# RCJ_com_v2.net
KiCad netlist of a schematic drawn in EAGLE
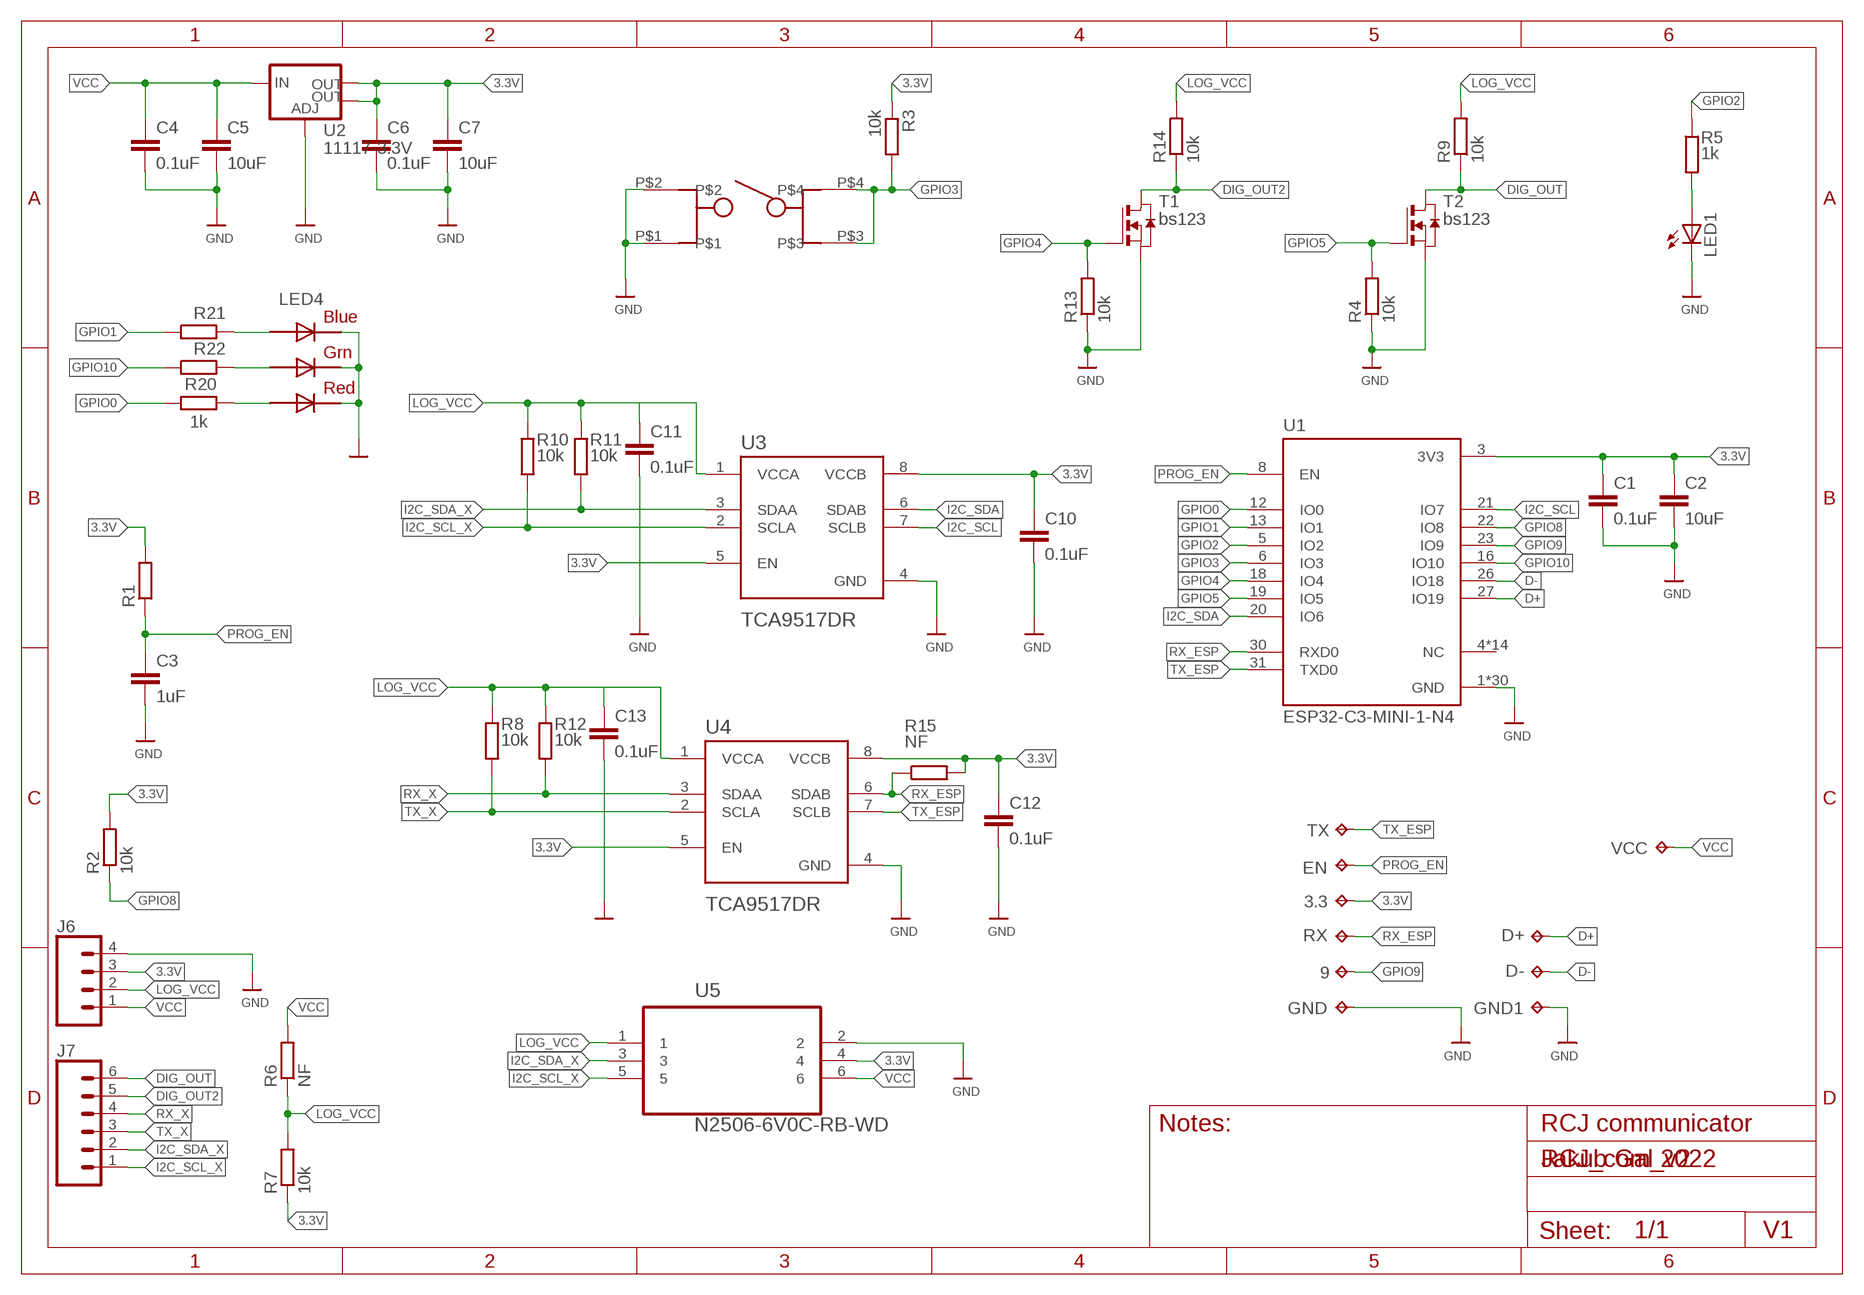
[diagram p0: schematic, sheet 1]

(export (version "E")
  (design (tool "Eeschema 10.0.6"))
  (components
    (comp (ref "3.3")
      (value "TPTP08R")
      (footprint "eagle-import:TP08R")
      (libsource (lib "eagle-import") (part "TPTP08R"))
    )
    (comp (ref "9")
      (value "TPTP08R")
      (footprint "eagle-import:TP08R")
      (libsource (lib "eagle-import") (part "TPTP08R"))
    )
    (comp (ref "C1")
      (value "0.1uF")
      (footprint "eagle-import:C0402K")
      (libsource (lib "eagle-import") (part "C-EUC0402K"))
    )
    (comp (ref "C2")
      (value "10uF")
      (footprint "eagle-import:C0402K")
      (libsource (lib "eagle-import") (part "C-EUC0402K"))
    )
    (comp (ref "C3")
      (value "1uF")
      (footprint "eagle-import:C0402K")
      (libsource (lib "eagle-import") (part "C-EUC0402K"))
    )
    (comp (ref "C4")
      (value "0.1uF")
      (footprint "eagle-import:C0402K")
      (libsource (lib "eagle-import") (part "C-EUC0402K"))
    )
    (comp (ref "C5")
      (value "10uF")
      (footprint "eagle-import:C0402K")
      (libsource (lib "eagle-import") (part "C-EUC0402K"))
    )
    (comp (ref "C6")
      (value "0.1uF")
      (footprint "eagle-import:C0402K")
      (libsource (lib "eagle-import") (part "C-EUC0402K"))
    )
    (comp (ref "C7")
      (value "10uF")
      (footprint "eagle-import:C0402K")
      (libsource (lib "eagle-import") (part "C-EUC0402K"))
    )
    (comp (ref "C10")
      (value "0.1uF")
      (footprint "eagle-import:C0402K")
      (libsource (lib "eagle-import") (part "C-EUC0402K"))
    )
    (comp (ref "C11")
      (value "0.1uF")
      (footprint "eagle-import:C0402K")
      (libsource (lib "eagle-import") (part "C-EUC0402K"))
    )
    (comp (ref "C12")
      (value "0.1uF")
      (footprint "eagle-import:C0402K")
      (libsource (lib "eagle-import") (part "C-EUC0402K"))
    )
    (comp (ref "C13")
      (value "0.1uF")
      (footprint "eagle-import:C0402K")
      (libsource (lib "eagle-import") (part "C-EUC0402K"))
    )
    (comp (ref "D+")
      (value "TPTP08R")
      (footprint "eagle-import:TP08R")
      (libsource (lib "eagle-import") (part "TPTP08R"))
    )
    (comp (ref "D-")
      (value "TPTP08R")
      (footprint "eagle-import:TP08R")
      (libsource (lib "eagle-import") (part "TPTP08R"))
    )
    (comp (ref "EN")
      (value "TPTP08R")
      (footprint "eagle-import:TP08R")
      (libsource (lib "eagle-import") (part "TPTP08R"))
    )
    (comp (ref "GND")
      (value "TPTP08R")
      (footprint "eagle-import:TP08R")
      (libsource (lib "eagle-import") (part "TPTP08R"))
    )
    (comp (ref "GND1")
      (value "TPTP08R")
      (footprint "eagle-import:TP08R")
      (libsource (lib "eagle-import") (part "TPTP08R"))
    )
    (comp (ref "J6")
      (value "CONN_04")
      (footprint "eagle-import:1X04")
      (libsource (lib "eagle-import") (part "CONN_04"))
    )
    (comp (ref "J7")
      (value "CONN_06SILK_FEMALE_PTH")
      (footprint "eagle-import:1X06")
      (libsource (lib "eagle-import") (part "CONN_06SILK_FEMALE_PTH"))
    )
    (comp (ref "LED1")
      (value "0603_Led")
      (footprint "eagle-import:CHIPLED_0603")
      (libsource (lib "eagle-import") (part "LEDCHIPLED_0603"))
    )
    (comp (ref "LED4")
      (value "RGBLED5050")
      (footprint "eagle-import:RGBLED5050")
      (libsource (lib "eagle-import") (part "RGBLED5050"))
    )
    (comp (ref "R1")
      (value "10k")
      (footprint "eagle-import:R0402")
      (libsource (lib "eagle-import") (part "R-EU_R0402"))
    )
    (comp (ref "R2")
      (value "10k")
      (footprint "eagle-import:R0402")
      (libsource (lib "eagle-import") (part "R-EU_R0402"))
    )
    (comp (ref "R3")
      (value "10k")
      (footprint "eagle-import:R0402")
      (libsource (lib "eagle-import") (part "R-EU_R0402"))
    )
    (comp (ref "R4")
      (value "10k")
      (footprint "eagle-import:R0402")
      (libsource (lib "eagle-import") (part "R-EU_R0402"))
    )
    (comp (ref "R5")
      (value "1k")
      (footprint "eagle-import:R0402")
      (libsource (lib "eagle-import") (part "R-EU_R0402"))
    )
    (comp (ref "R6")
      (value "NF")
      (footprint "eagle-import:R0402")
      (libsource (lib "eagle-import") (part "R-EU_R0402"))
    )
    (comp (ref "R7")
      (value "10k")
      (footprint "eagle-import:R0402")
      (libsource (lib "eagle-import") (part "R-EU_R0402"))
    )
    (comp (ref "R8")
      (value "10k")
      (footprint "eagle-import:R0402")
      (libsource (lib "eagle-import") (part "R-EU_R0402"))
    )
    (comp (ref "R9")
      (value "10k")
      (footprint "eagle-import:R0402")
      (libsource (lib "eagle-import") (part "R-EU_R0402"))
    )
    (comp (ref "R10")
      (value "10k")
      (footprint "eagle-import:R0402")
      (libsource (lib "eagle-import") (part "R-EU_R0402"))
    )
    (comp (ref "R11")
      (value "10k")
      (footprint "eagle-import:R0402")
      (libsource (lib "eagle-import") (part "R-EU_R0402"))
    )
    (comp (ref "R12")
      (value "10k")
      (footprint "eagle-import:R0402")
      (libsource (lib "eagle-import") (part "R-EU_R0402"))
    )
    (comp (ref "R13")
      (value "10k")
      (footprint "eagle-import:R0402")
      (libsource (lib "eagle-import") (part "R-EU_R0402"))
    )
    (comp (ref "R14")
      (value "10k")
      (footprint "eagle-import:R0402")
      (libsource (lib "eagle-import") (part "R-EU_R0402"))
    )
    (comp (ref "R15")
      (value "NF")
      (footprint "eagle-import:R0402")
      (libsource (lib "eagle-import") (part "R-EU_R0402"))
    )
    (comp (ref "R20")
      (value "1k")
      (footprint "eagle-import:R0402")
      (libsource (lib "eagle-import") (part "R-EU_R0402"))
    )
    (comp (ref "R21")
      (value "1k")
      (footprint "eagle-import:R0402")
      (libsource (lib "eagle-import") (part "R-EU_R0402"))
    )
    (comp (ref "R22")
      (value "1k")
      (footprint "eagle-import:R0402")
      (libsource (lib "eagle-import") (part "R-EU_R0402"))
    )
    (comp (ref "RX")
      (value "TPTP08R")
      (footprint "eagle-import:TP08R")
      (libsource (lib "eagle-import") (part "TPTP08R"))
    )
    (comp (ref "T1")
      (value "bs123")
      (footprint "eagle-import:SOT-23")
      (libsource (lib "eagle-import") (part "NMOSSOT23"))
    )
    (comp (ref "T2")
      (value "bs123")
      (footprint "eagle-import:SOT-23")
      (libsource (lib "eagle-import") (part "NMOSSOT23"))
    )
    (comp (ref "TX")
      (value "TPTP08R")
      (footprint "eagle-import:TP08R")
      (libsource (lib "eagle-import") (part "TPTP08R"))
    )
    (comp (ref "U$9")
      (value "BUTON")
      (footprint "eagle-import:PBUTON_LSCS")
      (libsource (lib "eagle-import") (part "BUTON"))
    )
    (comp (ref "U1")
      (value "ESP32-C3-MINI-1-N4")
      (footprint "eagle-import:XCVR_ESP32-C3-MINI-1-N4")
      (fields (field (name "MF") "Espressif Systems"))
      (libsource (lib "eagle-import") (part "ESP32-C3-MINI-1-N4"))
    )
    (comp (ref "U2")
      (value "11117-3.3V")
      (footprint "eagle-import:SOT223")
      (libsource (lib "eagle-import") (part "V_REG_LM1117SOT223"))
    )
    (comp (ref "U3")
      (value "TCA9517DR")
      (footprint "eagle-import:SOIC127P599X175-8N")
      (fields (field (name "MF") "Texas Instruments"))
      (libsource (lib "eagle-import") (part "TCA9517DR"))
    )
    (comp (ref "U4")
      (value "TCA9517DR")
      (footprint "eagle-import:SOIC127P599X175-8N")
      (fields (field (name "MF") "Texas Instruments"))
      (libsource (lib "eagle-import") (part "TCA9517DR"))
    )
    (comp (ref "U5")
      (value "N2506-6V0C-RB-WD")
      (footprint "eagle-import:3M_N2506-6V0C-RB-WD")
      (fields (field (name "MF") "3M") (field (name "MP") "N2510-6V0C-RB-WD"))
      (libsource (lib "eagle-import") (part "N2506-6V0C-RB-WD"))
    )
    (comp (ref "VCC")
      (value "TPTP08R")
      (footprint "eagle-import:TP08R")
      (libsource (lib "eagle-import") (part "TPTP08R"))
    )
  )
  (nets
    (net (code "1") (name "3.3V") (class "Default")
      (node (ref "3.3") (pin "TP") (pinfunction "TP_TP") (pintype "input"))
      (node (ref "C1") (pin "1") (pinfunction "1_1") (pintype "passive"))
      (node (ref "C10") (pin "1") (pinfunction "1_1") (pintype "passive"))
      (node (ref "C12") (pin "1") (pinfunction "1_1") (pintype "passive"))
      (node (ref "C2") (pin "1") (pinfunction "1_1") (pintype "passive"))
      (node (ref "C6") (pin "1") (pinfunction "1_1") (pintype "passive"))
      (node (ref "C7") (pin "1") (pinfunction "1_1") (pintype "passive"))
      (node (ref "J6") (pin "3") (pinfunction "3_3") (pintype "passive"))
      (node (ref "R1") (pin "2") (pinfunction "2_2") (pintype "passive"))
      (node (ref "R15") (pin "2") (pinfunction "2_2") (pintype "passive"))
      (node (ref "R2") (pin "2") (pinfunction "2_2") (pintype "passive"))
      (node (ref "R3") (pin "1") (pinfunction "1_1") (pintype "passive"))
      (node (ref "R7") (pin "1") (pinfunction "1_1") (pintype "passive"))
      (node (ref "U1") (pin "3") (pinfunction "3V3_3") (pintype "power_in"))
      (node (ref "U2") (pin "2") (pinfunction "OUT_2") (pintype "output"))
      (node (ref "U2") (pin "4") (pinfunction "OUT_4") (pintype "output"))
      (node (ref "U3") (pin "5") (pinfunction "EN_5") (pintype "input"))
      (node (ref "U3") (pin "8") (pinfunction "VCCB_8") (pintype "power_in"))
      (node (ref "U4") (pin "5") (pinfunction "EN_5") (pintype "input"))
      (node (ref "U4") (pin "8") (pinfunction "VCCB_8") (pintype "power_in"))
      (node (ref "U5") (pin "4") (pinfunction "4_4") (pintype "passive"))
    )
    (net (code "2") (name "D+") (class "Default")
      (node (ref "D+") (pin "TP") (pinfunction "TP_TP") (pintype "input"))
      (node (ref "U1") (pin "27") (pinfunction "IO19_27") (pintype "bidirectional"))
    )
    (net (code "3") (name "D-") (class "Default")
      (node (ref "D-") (pin "TP") (pinfunction "TP_TP") (pintype "input"))
      (node (ref "U1") (pin "26") (pinfunction "IO18_26") (pintype "bidirectional"))
    )
    (net (code "4") (name "DIG_OUT") (class "Default")
      (node (ref "J7") (pin "6") (pinfunction "6_6") (pintype "passive"))
      (node (ref "R9") (pin "1") (pinfunction "1_1") (pintype "passive"))
      (node (ref "T2") (pin "1") (pinfunction "D_1") (pintype "passive"))
    )
    (net (code "5") (name "DIG_OUT2") (class "Default")
      (node (ref "J7") (pin "5") (pinfunction "5_5") (pintype "passive"))
      (node (ref "R14") (pin "1") (pinfunction "1_1") (pintype "passive"))
      (node (ref "T1") (pin "1") (pinfunction "D_1") (pintype "passive"))
    )
    (net (code "6") (name "GND") (class "Default")
      (node (ref "C1") (pin "2") (pinfunction "2_2") (pintype "passive"))
      (node (ref "C10") (pin "2") (pinfunction "2_2") (pintype "passive"))
      (node (ref "C11") (pin "2") (pinfunction "2_2") (pintype "passive"))
      (node (ref "C12") (pin "2") (pinfunction "2_2") (pintype "passive"))
      (node (ref "C13") (pin "2") (pinfunction "2_2") (pintype "passive"))
      (node (ref "C2") (pin "2") (pinfunction "2_2") (pintype "passive"))
      (node (ref "C3") (pin "2") (pinfunction "2_2") (pintype "passive"))
      (node (ref "C4") (pin "2") (pinfunction "2_2") (pintype "passive"))
      (node (ref "C5") (pin "2") (pinfunction "2_2") (pintype "passive"))
      (node (ref "C6") (pin "2") (pinfunction "2_2") (pintype "passive"))
      (node (ref "C7") (pin "2") (pinfunction "2_2") (pintype "passive"))
      (node (ref "GND") (pin "TP") (pinfunction "TP_TP") (pintype "input"))
      (node (ref "GND1") (pin "TP") (pinfunction "TP_TP") (pintype "input"))
      (node (ref "J6") (pin "4") (pinfunction "4_4") (pintype "passive"))
      (node (ref "LED1") (pin "C") (pinfunction "C_C") (pintype "passive"))
      (node (ref "LED4") (pin "4") (pinfunction "BLUE_C_4") (pintype "bidirectional"))
      (node (ref "LED4") (pin "5") (pinfunction "RED_C_5") (pintype "bidirectional"))
      (node (ref "LED4") (pin "6") (pinfunction "GREEN_C_6") (pintype "bidirectional"))
      (node (ref "R13") (pin "1") (pinfunction "1_1") (pintype "passive"))
      (node (ref "R4") (pin "1") (pinfunction "1_1") (pintype "passive"))
      (node (ref "T1") (pin "2") (pinfunction "S_2") (pintype "passive"))
      (node (ref "T2") (pin "2") (pinfunction "S_2") (pintype "passive"))
      (node (ref "U$9") (pin "P$1") (pinfunction "P$1_P$1") (pintype "bidirectional"))
      (node (ref "U$9") (pin "P$2") (pinfunction "P$2_P$2") (pintype "bidirectional"))
      (node (ref "U1") (pin "1") (pinfunction "GND_1") (pintype "power_in"))
      (node (ref "U1") (pin "11") (pinfunction "GND_11") (pintype "power_in"))
      (node (ref "U1") (pin "14") (pinfunction "GND_14") (pintype "power_in"))
      (node (ref "U1") (pin "2") (pinfunction "GND_2") (pintype "power_in"))
      (node (ref "U1") (pin "36") (pinfunction "GND_36") (pintype "power_in"))
      (node (ref "U1") (pin "37") (pinfunction "GND_37") (pintype "power_in"))
      (node (ref "U1") (pin "38") (pinfunction "GND_38") (pintype "power_in"))
      (node (ref "U1") (pin "39") (pinfunction "GND_39") (pintype "power_in"))
      (node (ref "U1") (pin "40") (pinfunction "GND_40") (pintype "power_in"))
      (node (ref "U1") (pin "41") (pinfunction "GND_41") (pintype "power_in"))
      (node (ref "U1") (pin "42") (pinfunction "GND_42") (pintype "power_in"))
      (node (ref "U1") (pin "43") (pinfunction "GND_43") (pintype "power_in"))
      (node (ref "U1") (pin "44") (pinfunction "GND_44") (pintype "power_in"))
      (node (ref "U1") (pin "45") (pinfunction "GND_45") (pintype "power_in"))
      (node (ref "U1") (pin "46") (pinfunction "GND_46") (pintype "power_in"))
      (node (ref "U1") (pin "47") (pinfunction "GND_47") (pintype "power_in"))
      (node (ref "U1") (pin "48") (pinfunction "GND_48") (pintype "power_in"))
      (node (ref "U1") (pin "49_1") (pinfunction "GND_49_1") (pintype "power_in"))
      (node (ref "U1") (pin "49_2") (pinfunction "GND_49_2") (pintype "power_in"))
      (node (ref "U1") (pin "49_3") (pinfunction "GND_49_3") (pintype "power_in"))
      (node (ref "U1") (pin "49_4") (pinfunction "GND_49_4") (pintype "power_in"))
      (node (ref "U1") (pin "49_5") (pinfunction "GND_49_5") (pintype "power_in"))
      (node (ref "U1") (pin "49_6") (pinfunction "GND_49_6") (pintype "power_in"))
      (node (ref "U1") (pin "49_7") (pinfunction "GND_49_7") (pintype "power_in"))
      (node (ref "U1") (pin "49_8") (pinfunction "GND_49_8") (pintype "power_in"))
      (node (ref "U1") (pin "49_9") (pinfunction "GND_49_9") (pintype "power_in"))
      (node (ref "U1") (pin "50") (pinfunction "GND_50") (pintype "power_in"))
      (node (ref "U1") (pin "51") (pinfunction "GND_51") (pintype "power_in"))
      (node (ref "U1") (pin "52") (pinfunction "GND_52") (pintype "power_in"))
      (node (ref "U1") (pin "53") (pinfunction "GND_53") (pintype "power_in"))
      (node (ref "U2") (pin "1") (pinfunction "ADJ_1") (pintype "input"))
      (node (ref "U3") (pin "4") (pinfunction "GND_4") (pintype "power_in"))
      (node (ref "U4") (pin "4") (pinfunction "GND_4") (pintype "power_in"))
      (node (ref "U5") (pin "2") (pinfunction "2_2") (pintype "passive"))
    )
    (net (code "7") (name "GPIO0") (class "Default")
      (node (ref "R20") (pin "1") (pinfunction "1_1") (pintype "passive"))
      (node (ref "U1") (pin "12") (pinfunction "IO0_12") (pintype "bidirectional"))
    )
    (net (code "8") (name "GPIO1") (class "Default")
      (node (ref "R21") (pin "1") (pinfunction "1_1") (pintype "passive"))
      (node (ref "U1") (pin "13") (pinfunction "IO1_13") (pintype "bidirectional"))
    )
    (net (code "9") (name "GPIO2") (class "Default")
      (node (ref "R5") (pin "1") (pinfunction "1_1") (pintype "passive"))
      (node (ref "U1") (pin "5") (pinfunction "IO2_5") (pintype "bidirectional"))
    )
    (net (code "10") (name "GPIO3") (class "Default")
      (node (ref "R3") (pin "2") (pinfunction "2_2") (pintype "passive"))
      (node (ref "U$9") (pin "P$3") (pinfunction "P$3_P$3") (pintype "bidirectional"))
      (node (ref "U$9") (pin "P$4") (pinfunction "P$4_P$4") (pintype "bidirectional"))
      (node (ref "U1") (pin "6") (pinfunction "IO3_6") (pintype "bidirectional"))
    )
    (net (code "11") (name "GPIO4") (class "Default")
      (node (ref "R13") (pin "2") (pinfunction "2_2") (pintype "passive"))
      (node (ref "T1") (pin "3") (pinfunction "G_3") (pintype "passive"))
      (node (ref "U1") (pin "18") (pinfunction "IO4_18") (pintype "bidirectional"))
    )
    (net (code "12") (name "GPIO5") (class "Default")
      (node (ref "R4") (pin "2") (pinfunction "2_2") (pintype "passive"))
      (node (ref "T2") (pin "3") (pinfunction "G_3") (pintype "passive"))
      (node (ref "U1") (pin "19") (pinfunction "IO5_19") (pintype "bidirectional"))
    )
    (net (code "13") (name "GPIO8") (class "Default")
      (node (ref "R2") (pin "1") (pinfunction "1_1") (pintype "passive"))
      (node (ref "U1") (pin "22") (pinfunction "IO8_22") (pintype "bidirectional"))
    )
    (net (code "14") (name "GPIO9") (class "Default")
      (node (ref "9") (pin "TP") (pinfunction "TP_TP") (pintype "input"))
      (node (ref "U1") (pin "23") (pinfunction "IO9_23") (pintype "bidirectional"))
    )
    (net (code "15") (name "GPIO10") (class "Default")
      (node (ref "R22") (pin "1") (pinfunction "1_1") (pintype "passive"))
      (node (ref "U1") (pin "16") (pinfunction "IO10_16") (pintype "bidirectional"))
    )
    (net (code "16") (name "I2C_SCL") (class "Default")
      (node (ref "U1") (pin "21") (pinfunction "IO7_21") (pintype "bidirectional"))
      (node (ref "U3") (pin "7") (pinfunction "SCLB_7") (pintype "bidirectional"))
    )
    (net (code "17") (name "I2C_SCL_X") (class "Default")
      (node (ref "J7") (pin "1") (pinfunction "1_1") (pintype "passive"))
      (node (ref "R10") (pin "2") (pinfunction "2_2") (pintype "passive"))
      (node (ref "U3") (pin "2") (pinfunction "SCLA_2") (pintype "bidirectional"))
      (node (ref "U5") (pin "5") (pinfunction "5_5") (pintype "passive"))
    )
    (net (code "18") (name "I2C_SDA") (class "Default")
      (node (ref "U1") (pin "20") (pinfunction "IO6_20") (pintype "bidirectional"))
      (node (ref "U3") (pin "6") (pinfunction "SDAB_6") (pintype "bidirectional"))
    )
    (net (code "19") (name "I2C_SDA_X") (class "Default")
      (node (ref "J7") (pin "2") (pinfunction "2_2") (pintype "passive"))
      (node (ref "R11") (pin "2") (pinfunction "2_2") (pintype "passive"))
      (node (ref "U3") (pin "3") (pinfunction "SDAA_3") (pintype "bidirectional"))
      (node (ref "U5") (pin "3") (pinfunction "3_3") (pintype "passive"))
    )
    (net (code "20") (name "LOG_VCC") (class "Default")
      (node (ref "C11") (pin "1") (pinfunction "1_1") (pintype "passive"))
      (node (ref "C13") (pin "1") (pinfunction "1_1") (pintype "passive"))
      (node (ref "J6") (pin "2") (pinfunction "2_2") (pintype "passive"))
      (node (ref "R10") (pin "1") (pinfunction "1_1") (pintype "passive"))
      (node (ref "R11") (pin "1") (pinfunction "1_1") (pintype "passive"))
      (node (ref "R12") (pin "1") (pinfunction "1_1") (pintype "passive"))
      (node (ref "R14") (pin "2") (pinfunction "2_2") (pintype "passive"))
      (node (ref "R6") (pin "1") (pinfunction "1_1") (pintype "passive"))
      (node (ref "R7") (pin "2") (pinfunction "2_2") (pintype "passive"))
      (node (ref "R8") (pin "1") (pinfunction "1_1") (pintype "passive"))
      (node (ref "R9") (pin "2") (pinfunction "2_2") (pintype "passive"))
      (node (ref "U3") (pin "1") (pinfunction "VCCA_1") (pintype "power_in"))
      (node (ref "U4") (pin "1") (pinfunction "VCCA_1") (pintype "power_in"))
      (node (ref "U5") (pin "1") (pinfunction "1_1") (pintype "passive"))
    )
    (net (code "21") (name "Net-(LED1-PadA)") (class "Default")
      (node (ref "LED1") (pin "A") (pinfunction "A_A") (pintype "passive"))
      (node (ref "R5") (pin "2") (pinfunction "2_2") (pintype "passive"))
    )
    (net (code "22") (name "Net-(LED4-BLUE_A)") (class "Default")
      (node (ref "LED4") (pin "3") (pinfunction "BLUE_A_3") (pintype "bidirectional"))
      (node (ref "R21") (pin "2") (pinfunction "2_2") (pintype "passive"))
    )
    (net (code "23") (name "Net-(LED4-GREEN_A)") (class "Default")
      (node (ref "LED4") (pin "1") (pinfunction "GREEN_A_1") (pintype "bidirectional"))
      (node (ref "R22") (pin "2") (pinfunction "2_2") (pintype "passive"))
    )
    (net (code "24") (name "Net-(LED4-RED_A)") (class "Default")
      (node (ref "LED4") (pin "2") (pinfunction "RED_A_2") (pintype "bidirectional"))
      (node (ref "R20") (pin "2") (pinfunction "2_2") (pintype "passive"))
    )
    (net (code "25") (name "PROG_EN") (class "Default")
      (node (ref "C3") (pin "1") (pinfunction "1_1") (pintype "passive"))
      (node (ref "EN") (pin "TP") (pinfunction "TP_TP") (pintype "input"))
      (node (ref "R1") (pin "1") (pinfunction "1_1") (pintype "passive"))
      (node (ref "U1") (pin "8") (pinfunction "EN_8") (pintype "input"))
    )
    (net (code "26") (name "RX_ESP") (class "Default")
      (node (ref "R15") (pin "1") (pinfunction "1_1") (pintype "passive"))
      (node (ref "RX") (pin "TP") (pinfunction "TP_TP") (pintype "input"))
      (node (ref "U1") (pin "30") (pinfunction "RXD0_30") (pintype "bidirectional"))
      (node (ref "U4") (pin "6") (pinfunction "SDAB_6") (pintype "bidirectional"))
    )
    (net (code "27") (name "RX_X") (class "Default")
      (node (ref "J7") (pin "4") (pinfunction "4_4") (pintype "passive"))
      (node (ref "R12") (pin "2") (pinfunction "2_2") (pintype "passive"))
      (node (ref "U4") (pin "3") (pinfunction "SDAA_3") (pintype "bidirectional"))
    )
    (net (code "28") (name "TX_ESP") (class "Default")
      (node (ref "TX") (pin "TP") (pinfunction "TP_TP") (pintype "input"))
      (node (ref "U1") (pin "31") (pinfunction "TXD0_31") (pintype "bidirectional"))
      (node (ref "U4") (pin "7") (pinfunction "SCLB_7") (pintype "bidirectional"))
    )
    (net (code "29") (name "TX_X") (class "Default")
      (node (ref "J7") (pin "3") (pinfunction "3_3") (pintype "passive"))
      (node (ref "R8") (pin "2") (pinfunction "2_2") (pintype "passive"))
      (node (ref "U4") (pin "2") (pinfunction "SCLA_2") (pintype "bidirectional"))
    )
    (net (code "30") (name "VCC") (class "Default")
      (node (ref "C4") (pin "1") (pinfunction "1_1") (pintype "passive"))
      (node (ref "C5") (pin "1") (pinfunction "1_1") (pintype "passive"))
      (node (ref "J6") (pin "1") (pinfunction "1_1") (pintype "passive"))
      (node (ref "R6") (pin "2") (pinfunction "2_2") (pintype "passive"))
      (node (ref "U2") (pin "3") (pinfunction "IN_3") (pintype "input"))
      (node (ref "U5") (pin "6") (pinfunction "6_6") (pintype "passive"))
      (node (ref "VCC") (pin "TP") (pinfunction "TP_TP") (pintype "input"))
    )
    (net (code "31") (name "unconnected-(U1-NC-Pad4)") (class "Default")
      (node (ref "U1") (pin "4") (pinfunction "NC_4") (pintype "no_connect"))
    )
    (net (code "32") (name "unconnected-(U1-NC-Pad7)") (class "Default")
      (node (ref "U1") (pin "7") (pinfunction "NC_7") (pintype "no_connect"))
    )
    (net (code "33") (name "unconnected-(U1-NC-Pad9)") (class "Default")
      (node (ref "U1") (pin "9") (pinfunction "NC_9") (pintype "no_connect"))
    )
    (net (code "34") (name "unconnected-(U1-NC-Pad10)") (class "Default")
      (node (ref "U1") (pin "10") (pinfunction "NC_10") (pintype "no_connect"))
    )
    (net (code "35") (name "unconnected-(U1-NC-Pad15)") (class "Default")
      (node (ref "U1") (pin "15") (pinfunction "NC_15") (pintype "no_connect"))
    )
    (net (code "36") (name "unconnected-(U1-NC-Pad17)") (class "Default")
      (node (ref "U1") (pin "17") (pinfunction "NC_17") (pintype "no_connect"))
    )
    (net (code "37") (name "unconnected-(U1-NC-Pad24)") (class "Default")
      (node (ref "U1") (pin "24") (pinfunction "NC_24") (pintype "no_connect"))
    )
    (net (code "38") (name "unconnected-(U1-NC-Pad25)") (class "Default")
      (node (ref "U1") (pin "25") (pinfunction "NC_25") (pintype "no_connect"))
    )
    (net (code "39") (name "unconnected-(U1-NC-Pad28)") (class "Default")
      (node (ref "U1") (pin "28") (pinfunction "NC_28") (pintype "no_connect"))
    )
    (net (code "40") (name "unconnected-(U1-NC-Pad29)") (class "Default")
      (node (ref "U1") (pin "29") (pinfunction "NC_29") (pintype "no_connect"))
    )
    (net (code "41") (name "unconnected-(U1-NC-Pad32)") (class "Default")
      (node (ref "U1") (pin "32") (pinfunction "NC_32") (pintype "no_connect"))
    )
    (net (code "42") (name "unconnected-(U1-NC-Pad33)") (class "Default")
      (node (ref "U1") (pin "33") (pinfunction "NC_33") (pintype "no_connect"))
    )
    (net (code "43") (name "unconnected-(U1-NC-Pad34)") (class "Default")
      (node (ref "U1") (pin "34") (pinfunction "NC_34") (pintype "no_connect"))
    )
    (net (code "44") (name "unconnected-(U1-NC-Pad35)") (class "Default")
      (node (ref "U1") (pin "35") (pinfunction "NC_35") (pintype "no_connect"))
    )
  )
)
